# main_schematic.net
KiCad netlist of a schematic drawn in EAGLE
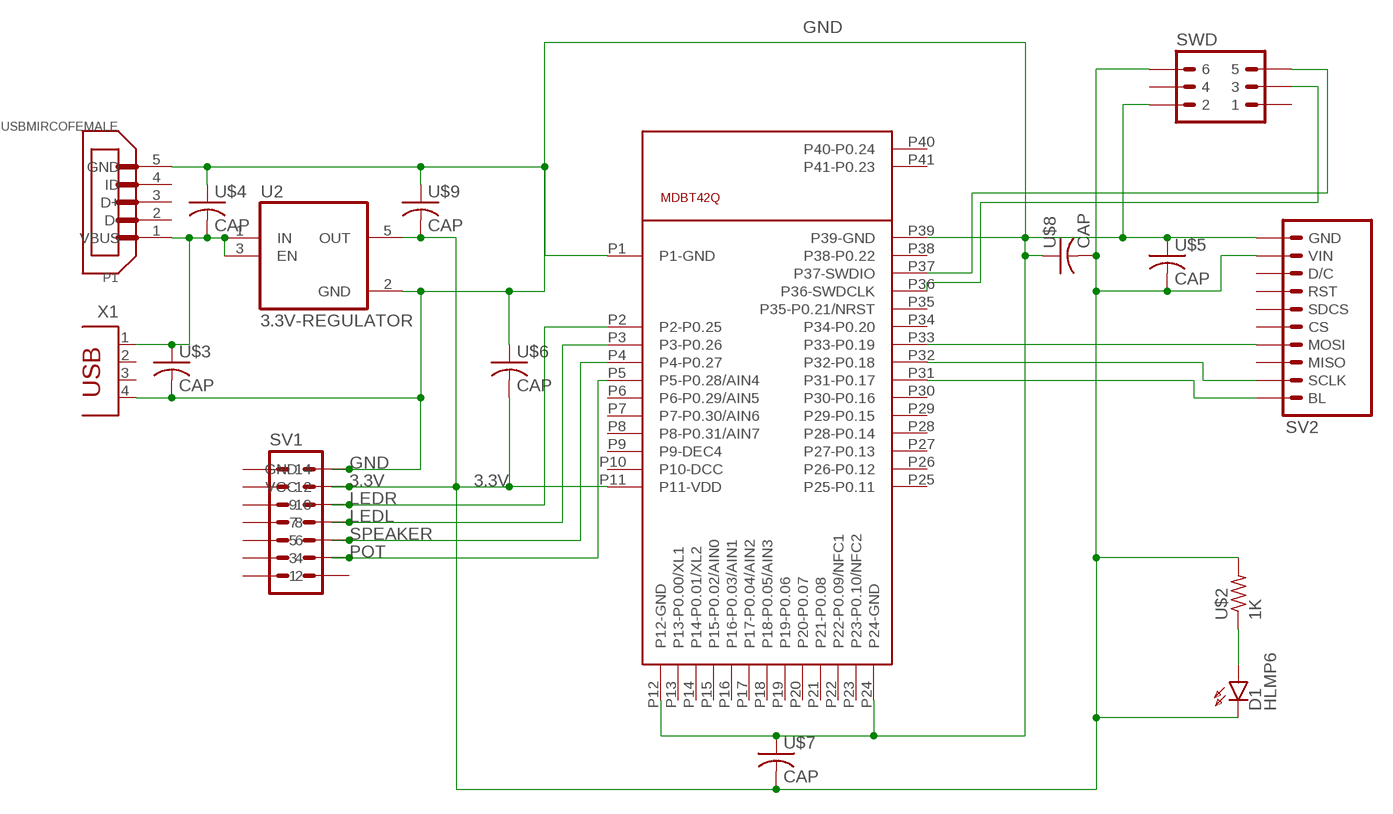
[diagram p0: schematic, sheet 1]

(export (version "E")
  (design (tool "Eeschema 10.0.6"))
  (components
    (comp (ref "D1")
      (value "HLMP6")
      (footprint "eagle-import:HLMP6")
      (fields (field (name "MF") "AGILENT TECHNOLOGIES") (field (name "MPN") "HLMP-6500"))
      (libsource (lib "eagle-import") (part "HLMP6"))
    )
    (comp (ref "P1")
      (value "USBMIRCOFEMALE")
      (footprint "eagle-import:MOLEX_0473460001")
      (fields (field (name "MF") "Weidmuller") (field (name "MP") "0473460001"))
      (libsource (lib "eagle-import") (part "USBMIRCOFEMALE"))
    )
    (comp (ref "SV1")
      (value "MISCHEADER")
      (footprint "eagle-import:MA07-2")
      (libsource (lib "eagle-import") (part "MISCHEADER"))
    )
    (comp (ref "SV2")
      (value "LCDHEADERS")
      (footprint "eagle-import:MA10-1")
      (libsource (lib "eagle-import") (part "LCDHEADERS"))
    )
    (comp (ref "SWD")
      (value "DEBUGGER")
      (footprint "eagle-import:MA03-2")
      (libsource (lib "eagle-import") (part "DEBUGGER"))
    )
    (comp (ref "U$1")
      (value "MDBT42Q")
      (footprint "eagle-import:MDBT40")
      (libsource (lib "eagle-import") (part "MDBT42Q"))
    )
    (comp (ref "U$2")
      (value "1K")
      (footprint "eagle-import:M1206")
      (libsource (lib "eagle-import") (part "RESISTOR"))
    )
    (comp (ref "U$3")
      (value "CAP")
      (footprint "eagle-import:C1206")
      (libsource (lib "eagle-import") (part "CAP"))
    )
    (comp (ref "U$4")
      (value "CAP")
      (footprint "eagle-import:C1206")
      (libsource (lib "eagle-import") (part "CAP"))
    )
    (comp (ref "U$5")
      (value "CAP")
      (footprint "eagle-import:C1206")
      (libsource (lib "eagle-import") (part "CAP"))
    )
    (comp (ref "U$6")
      (value "CAP")
      (footprint "eagle-import:C1206")
      (libsource (lib "eagle-import") (part "CAP"))
    )
    (comp (ref "U$7")
      (value "CAP")
      (footprint "eagle-import:C1206")
      (libsource (lib "eagle-import") (part "CAP"))
    )
    (comp (ref "U$8")
      (value "CAP")
      (footprint "eagle-import:C1206")
      (libsource (lib "eagle-import") (part "CAP"))
    )
    (comp (ref "U$9")
      (value "CAP")
      (footprint "eagle-import:C1206")
      (libsource (lib "eagle-import") (part "CAP"))
    )
    (comp (ref "U2")
      (value "3.3V-REGULATOR")
      (footprint "eagle-import:SOT95P280X145-5N")
      (fields (field (name "MF") "Texas Instruments") (field (name "MP") "TLV75533PDBVR"))
      (libsource (lib "eagle-import") (part "3.3V-REGULATOR"))
    )
    (comp (ref "X1")
      (value "USBCON")
      (footprint "eagle-import:PN87520")
      (libsource (lib "eagle-import") (part "USBCON"))
    )
  )
  (nets
    (net (code "1") (name "/3.3V") (class "Default")
      (node (ref "D1") (pin "K") (pinfunction "K_K") (pintype "passive"))
      (node (ref "SV1") (pin "11") (pinfunction "VCC_11") (pintype "passive"))
      (node (ref "SV2") (pin "2") (pinfunction "VIN_2") (pintype "passive"))
      (node (ref "SWD") (pin "6") (pinfunction "6_6") (pintype "passive"))
      (node (ref "U$1") (pin "P11") (pinfunction "P11-VDD_P11") (pintype "bidirectional"))
      (node (ref "U$2") (pin "2") (pinfunction "2_2") (pintype "passive"))
      (node (ref "U$5") (pin "2") (pinfunction "2_2") (pintype "passive"))
      (node (ref "U$6") (pin "2") (pinfunction "2_2") (pintype "passive"))
      (node (ref "U$7") (pin "2") (pinfunction "2_2") (pintype "passive"))
      (node (ref "U$8") (pin "2") (pinfunction "2_2") (pintype "passive"))
      (node (ref "U$9") (pin "2") (pinfunction "2_2") (pintype "passive"))
      (node (ref "U2") (pin "5") (pinfunction "OUT_5") (pintype "output"))
    )
    (net (code "2") (name "/GND") (class "Default")
      (node (ref "P1") (pin "5") (pinfunction "GND_5") (pintype "passive"))
      (node (ref "SV1") (pin "13") (pinfunction "GND_13") (pintype "passive"))
      (node (ref "SV2") (pin "1") (pinfunction "GND_1") (pintype "passive"))
      (node (ref "SWD") (pin "2") (pinfunction "2_2") (pintype "passive"))
      (node (ref "U$1") (pin "P1") (pinfunction "P1-GND_P1") (pintype "bidirectional"))
      (node (ref "U$1") (pin "P12") (pinfunction "P12-GND_P12") (pintype "bidirectional"))
      (node (ref "U$1") (pin "P24") (pinfunction "P24-GND_P24") (pintype "bidirectional"))
      (node (ref "U$1") (pin "P39") (pinfunction "P39-GND_P39") (pintype "bidirectional"))
      (node (ref "U$3") (pin "2") (pinfunction "2_2") (pintype "passive"))
      (node (ref "U$4") (pin "1") (pinfunction "1_1") (pintype "passive"))
      (node (ref "U$5") (pin "1") (pinfunction "1_1") (pintype "passive"))
      (node (ref "U$6") (pin "1") (pinfunction "1_1") (pintype "passive"))
      (node (ref "U$7") (pin "1") (pinfunction "1_1") (pintype "passive"))
      (node (ref "U$8") (pin "1") (pinfunction "1_1") (pintype "passive"))
      (node (ref "U$9") (pin "1") (pinfunction "1_1") (pintype "passive"))
      (node (ref "U2") (pin "2") (pinfunction "GND_2") (pintype "power_in"))
      (node (ref "X1") (pin "4") (pinfunction "4_4") (pintype "passive"))
    )
    (net (code "3") (name "/LEDL") (class "Default")
      (node (ref "SV1") (pin "7") (pinfunction "7_7") (pintype "passive"))
      (node (ref "U$1") (pin "P3") (pinfunction "P3-P0.26_P3") (pintype "bidirectional"))
    )
    (net (code "4") (name "/LEDR") (class "Default")
      (node (ref "SV1") (pin "9") (pinfunction "9_9") (pintype "passive"))
      (node (ref "U$1") (pin "P2") (pinfunction "P2-P0.25_P2") (pintype "bidirectional"))
    )
    (net (code "5") (name "/POT") (class "Default")
      (node (ref "SV1") (pin "3") (pinfunction "3_3") (pintype "passive"))
      (node (ref "U$1") (pin "P5") (pinfunction "P5-P0.28/AIN4_P5") (pintype "bidirectional"))
    )
    (net (code "6") (name "/SPEAKER") (class "Default")
      (node (ref "SV1") (pin "5") (pinfunction "5_5") (pintype "passive"))
      (node (ref "U$1") (pin "P4") (pinfunction "P4-P0.27_P4") (pintype "bidirectional"))
    )
    (net (code "7") (name "Net-(D1-PadA)") (class "Default")
      (node (ref "D1") (pin "A") (pinfunction "A_A") (pintype "passive"))
      (node (ref "U$2") (pin "1") (pinfunction "1_1") (pintype "passive"))
    )
    (net (code "8") (name "Net-(P1-VBUS)") (class "Default")
      (node (ref "P1") (pin "1") (pinfunction "VBUS_1") (pintype "power_in"))
      (node (ref "U$3") (pin "1") (pinfunction "1_1") (pintype "passive"))
      (node (ref "U$4") (pin "2") (pinfunction "2_2") (pintype "passive"))
      (node (ref "U2") (pin "1") (pinfunction "IN_1") (pintype "input"))
      (node (ref "U2") (pin "3") (pinfunction "EN_3") (pintype "input"))
      (node (ref "X1") (pin "1") (pinfunction "1_1") (pintype "passive"))
    )
    (net (code "9") (name "Net-(SV2-BL)") (class "Default")
      (node (ref "SV2") (pin "10") (pinfunction "BL_10") (pintype "passive"))
      (node (ref "U$1") (pin "P31") (pinfunction "P31-P0.17_P31") (pintype "bidirectional"))
    )
    (net (code "10") (name "Net-(SV2-MOSI)") (class "Default")
      (node (ref "SV2") (pin "7") (pinfunction "MOSI_7") (pintype "passive"))
      (node (ref "U$1") (pin "P33") (pinfunction "P33-P0.19_P33") (pintype "bidirectional"))
    )
    (net (code "11") (name "Net-(SV2-SCLK)") (class "Default")
      (node (ref "SV2") (pin "9") (pinfunction "SCLK_9") (pintype "passive"))
      (node (ref "U$1") (pin "P32") (pinfunction "P32-P0.18_P32") (pintype "bidirectional"))
    )
    (net (code "12") (name "Net-(U$1-P36-SWDCLK)") (class "Default")
      (node (ref "SWD") (pin "3") (pinfunction "3_3") (pintype "passive"))
      (node (ref "U$1") (pin "P36") (pinfunction "P36-SWDCLK_P36") (pintype "bidirectional"))
    )
    (net (code "13") (name "Net-(U$1-P37-SWDIO)") (class "Default")
      (node (ref "SWD") (pin "5") (pinfunction "5_5") (pintype "passive"))
      (node (ref "U$1") (pin "P37") (pinfunction "P37-SWDIO_P37") (pintype "bidirectional"))
    )
    (net (code "14") (name "unconnected-(P1-D+-Pad3)") (class "Default")
      (node (ref "P1") (pin "3") (pinfunction "D+_3") (pintype "bidirectional"))
    )
    (net (code "15") (name "unconnected-(P1-D--Pad2)") (class "Default")
      (node (ref "P1") (pin "2") (pinfunction "D-_2") (pintype "bidirectional"))
    )
    (net (code "16") (name "unconnected-(P1-ID-Pad4)") (class "Default")
      (node (ref "P1") (pin "4") (pinfunction "ID_4") (pintype "bidirectional"))
    )
    (net (code "17") (name "unconnected-(SV1-Pad1)") (class "Default")
      (node (ref "SV1") (pin "1") (pinfunction "1_1") (pintype "passive"))
    )
    (net (code "18") (name "unconnected-(SV1-Pad2)") (class "Default")
      (node (ref "SV1") (pin "2") (pinfunction "2_2") (pintype "passive"))
    )
    (net (code "19") (name "unconnected-(SV1-Pad4)") (class "Default")
      (node (ref "SV1") (pin "4") (pinfunction "4_4") (pintype "passive"))
    )
    (net (code "20") (name "unconnected-(SV1-Pad6)") (class "Default")
      (node (ref "SV1") (pin "6") (pinfunction "6_6") (pintype "passive"))
    )
    (net (code "21") (name "unconnected-(SV1-Pad8)") (class "Default")
      (node (ref "SV1") (pin "8") (pinfunction "8_8") (pintype "passive"))
    )
    (net (code "22") (name "unconnected-(SV1-Pad10)") (class "Default")
      (node (ref "SV1") (pin "10") (pinfunction "10_10") (pintype "passive"))
    )
    (net (code "23") (name "unconnected-(SV1-Pad12)") (class "Default")
      (node (ref "SV1") (pin "12") (pinfunction "12_12") (pintype "passive"))
    )
    (net (code "24") (name "unconnected-(SV1-Pad14)") (class "Default")
      (node (ref "SV1") (pin "14") (pinfunction "14_14") (pintype "passive"))
    )
    (net (code "25") (name "unconnected-(SV2-CS-Pad6)") (class "Default")
      (node (ref "SV2") (pin "6") (pinfunction "CS_6") (pintype "passive"))
    )
    (net (code "26") (name "unconnected-(SV2-D{slash}C-Pad3)") (class "Default")
      (node (ref "SV2") (pin "3") (pinfunction "D/C_3") (pintype "passive"))
    )
    (net (code "27") (name "unconnected-(SV2-MISO-Pad8)") (class "Default")
      (node (ref "SV2") (pin "8") (pinfunction "MISO_8") (pintype "passive"))
    )
    (net (code "28") (name "unconnected-(SV2-RST-Pad4)") (class "Default")
      (node (ref "SV2") (pin "4") (pinfunction "RST_4") (pintype "passive"))
    )
    (net (code "29") (name "unconnected-(SV2-SDCS-Pad5)") (class "Default")
      (node (ref "SV2") (pin "5") (pinfunction "SDCS_5") (pintype "passive"))
    )
    (net (code "30") (name "unconnected-(SWD-Pad1)") (class "Default")
      (node (ref "SWD") (pin "1") (pinfunction "1_1") (pintype "passive"))
    )
    (net (code "31") (name "unconnected-(SWD-Pad4)") (class "Default")
      (node (ref "SWD") (pin "4") (pinfunction "4_4") (pintype "passive"))
    )
    (net (code "32") (name "unconnected-(U$1-P6-P0.29{slash}AIN5-PadP6)") (class "Default")
      (node (ref "U$1") (pin "P6") (pinfunction "P6-P0.29/AIN5_P6") (pintype "bidirectional"))
    )
    (net (code "33") (name "unconnected-(U$1-P7-P0.30{slash}AIN6-PadP7)") (class "Default")
      (node (ref "U$1") (pin "P7") (pinfunction "P7-P0.30/AIN6_P7") (pintype "bidirectional"))
    )
    (net (code "34") (name "unconnected-(U$1-P8-P0.31{slash}AIN7-PadP8)") (class "Default")
      (node (ref "U$1") (pin "P8") (pinfunction "P8-P0.31/AIN7_P8") (pintype "bidirectional"))
    )
    (net (code "35") (name "unconnected-(U$1-P9-DEC4-PadP9)") (class "Default")
      (node (ref "U$1") (pin "P9") (pinfunction "P9-DEC4_P9") (pintype "bidirectional"))
    )
    (net (code "36") (name "unconnected-(U$1-P10-DCC-PadP10)") (class "Default")
      (node (ref "U$1") (pin "P10") (pinfunction "P10-DCC_P10") (pintype "bidirectional"))
    )
    (net (code "37") (name "unconnected-(U$1-P13-P0.00{slash}XL1-PadP13)") (class "Default")
      (node (ref "U$1") (pin "P13") (pinfunction "P13-P0.00/XL1_P13") (pintype "bidirectional"))
    )
    (net (code "38") (name "unconnected-(U$1-P14-P0.01{slash}XL2-PadP14)") (class "Default")
      (node (ref "U$1") (pin "P14") (pinfunction "P14-P0.01/XL2_P14") (pintype "bidirectional"))
    )
    (net (code "39") (name "unconnected-(U$1-P15-P0.02{slash}AIN0-PadP15)") (class "Default")
      (node (ref "U$1") (pin "P15") (pinfunction "P15-P0.02/AIN0_P15") (pintype "bidirectional"))
    )
    (net (code "40") (name "unconnected-(U$1-P16-P0.03{slash}AIN1-PadP16)") (class "Default")
      (node (ref "U$1") (pin "P16") (pinfunction "P16-P0.03/AIN1_P16") (pintype "bidirectional"))
    )
    (net (code "41") (name "unconnected-(U$1-P17-P0.04{slash}AIN2-PadP17)") (class "Default")
      (node (ref "U$1") (pin "P17") (pinfunction "P17-P0.04/AIN2_P17") (pintype "bidirectional"))
    )
    (net (code "42") (name "unconnected-(U$1-P18-P0.05{slash}AIN3-PadP18)") (class "Default")
      (node (ref "U$1") (pin "P18") (pinfunction "P18-P0.05/AIN3_P18") (pintype "bidirectional"))
    )
    (net (code "43") (name "unconnected-(U$1-P19-P0.06-PadP19)") (class "Default")
      (node (ref "U$1") (pin "P19") (pinfunction "P19-P0.06_P19") (pintype "bidirectional"))
    )
    (net (code "44") (name "unconnected-(U$1-P20-P0.07-PadP20)") (class "Default")
      (node (ref "U$1") (pin "P20") (pinfunction "P20-P0.07_P20") (pintype "bidirectional"))
    )
    (net (code "45") (name "unconnected-(U$1-P21-P0.08-PadP21)") (class "Default")
      (node (ref "U$1") (pin "P21") (pinfunction "P21-P0.08_P21") (pintype "bidirectional"))
    )
    (net (code "46") (name "unconnected-(U$1-P22-P0.09{slash}NFC1-PadP22)") (class "Default")
      (node (ref "U$1") (pin "P22") (pinfunction "P22-P0.09/NFC1_P22") (pintype "bidirectional"))
    )
    (net (code "47") (name "unconnected-(U$1-P23-P0.10{slash}NFC2-PadP23)") (class "Default")
      (node (ref "U$1") (pin "P23") (pinfunction "P23-P0.10/NFC2_P23") (pintype "bidirectional"))
    )
    (net (code "48") (name "unconnected-(U$1-P25-P0.11-PadP25)") (class "Default")
      (node (ref "U$1") (pin "P25") (pinfunction "P25-P0.11_P25") (pintype "bidirectional"))
    )
    (net (code "49") (name "unconnected-(U$1-P26-P0.12-PadP26)") (class "Default")
      (node (ref "U$1") (pin "P26") (pinfunction "P26-P0.12_P26") (pintype "bidirectional"))
    )
    (net (code "50") (name "unconnected-(U$1-P27-P0.13-PadP27)") (class "Default")
      (node (ref "U$1") (pin "P27") (pinfunction "P27-P0.13_P27") (pintype "bidirectional"))
    )
    (net (code "51") (name "unconnected-(U$1-P28-P0.14-PadP28)") (class "Default")
      (node (ref "U$1") (pin "P28") (pinfunction "P28-P0.14_P28") (pintype "bidirectional"))
    )
    (net (code "52") (name "unconnected-(U$1-P29-P0.15-PadP29)") (class "Default")
      (node (ref "U$1") (pin "P29") (pinfunction "P29-P0.15_P29") (pintype "bidirectional"))
    )
    (net (code "53") (name "unconnected-(U$1-P30-P0.16-PadP30)") (class "Default")
      (node (ref "U$1") (pin "P30") (pinfunction "P30-P0.16_P30") (pintype "bidirectional"))
    )
    (net (code "54") (name "unconnected-(U$1-P34-P0.20-PadP34)") (class "Default")
      (node (ref "U$1") (pin "P34") (pinfunction "P34-P0.20_P34") (pintype "bidirectional"))
    )
    (net (code "55") (name "unconnected-(U$1-P35-P0.21{slash}NRST-PadP35)") (class "Default")
      (node (ref "U$1") (pin "P35") (pinfunction "P35-P0.21/NRST_P35") (pintype "bidirectional"))
    )
    (net (code "56") (name "unconnected-(U$1-P38-P0.22-PadP38)") (class "Default")
      (node (ref "U$1") (pin "P38") (pinfunction "P38-P0.22_P38") (pintype "bidirectional"))
    )
    (net (code "57") (name "unconnected-(U$1-P40-P0.24-PadP40)") (class "Default")
      (node (ref "U$1") (pin "P40") (pinfunction "P40-P0.24_P40") (pintype "bidirectional"))
    )
    (net (code "58") (name "unconnected-(U$1-P41-P0.23-PadP41)") (class "Default")
      (node (ref "U$1") (pin "P41") (pinfunction "P41-P0.23_P41") (pintype "bidirectional"))
    )
    (net (code "59") (name "unconnected-(X1-Pad2)") (class "Default")
      (node (ref "X1") (pin "2") (pinfunction "2_2") (pintype "passive"))
    )
    (net (code "60") (name "unconnected-(X1-Pad3)") (class "Default")
      (node (ref "X1") (pin "3") (pinfunction "3_3") (pintype "passive"))
    )
  )
)
